# rapidshark-forward-breakout-mk-1_1.net
KiCad netlist of a schematic drawn in EAGLE
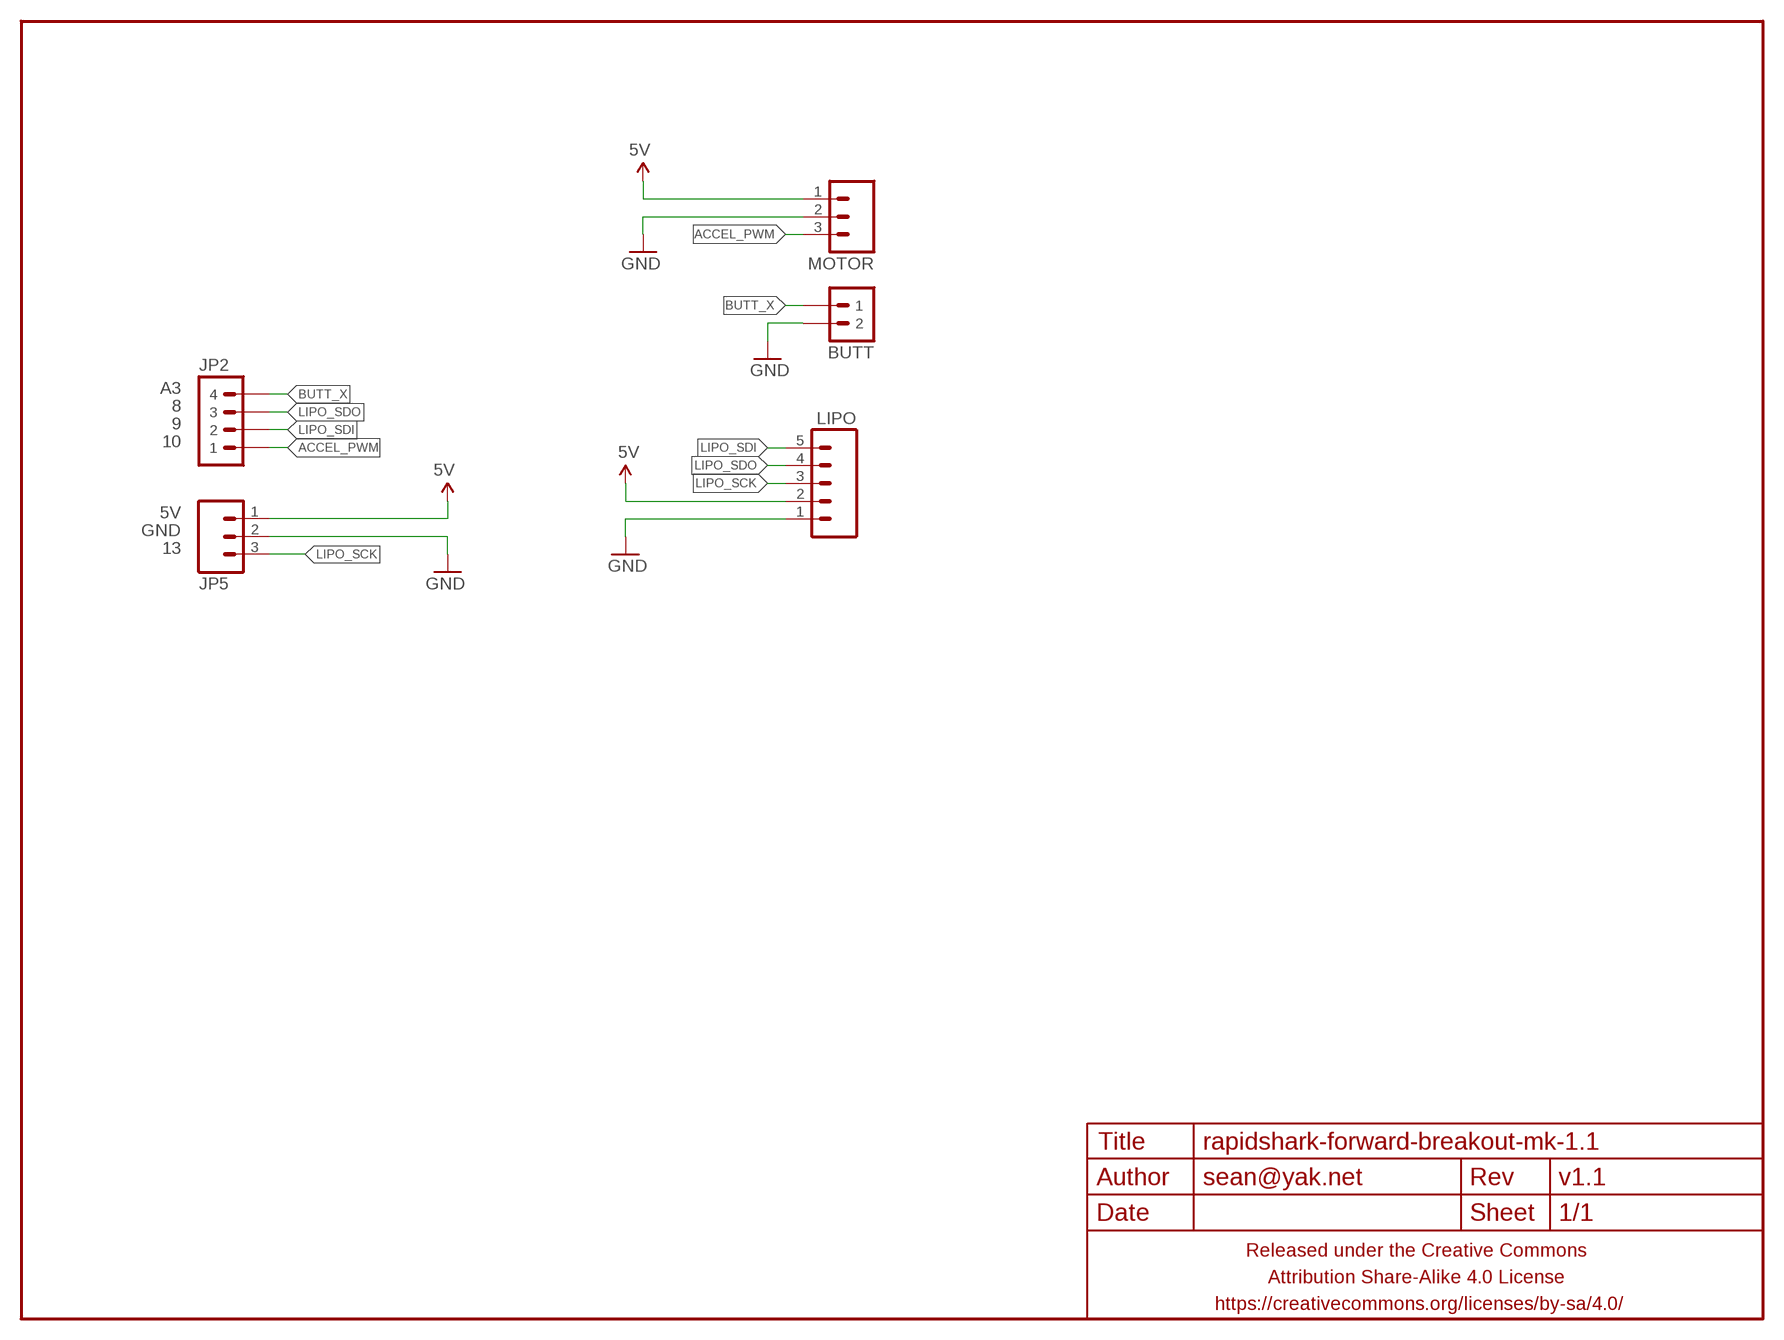
[diagram p0: schematic, sheet 1]

(export (version "E")
  (design (tool "Eeschema 10.0.6"))
  (components
    (comp (ref "BUTT")
      (value "M02JST-PTH-VERT")
      (footprint "eagle-import:JST-2-PH-VERT-PTH")
      (libsource (lib "eagle-import") (part "M02JST-PTH-VERT"))
    )
    (comp (ref "FRAME1")
      (value "FRAME-LETTERNO_PACKAGE")
      (footprint "eagle-import:DUMMY")
      (fields (field (name "DESIGNER") "sean@yak.net") (field (name "VERSION") "v1.1"))
      (libsource (lib "eagle-import") (part "FRAME-LETTERNO_PACKAGE"))
    )
    (comp (ref "JP2")
      (value "M04JST-PTH-VERT")
      (footprint "eagle-import:JST-4-PH-VERT-PTH")
      (libsource (lib "eagle-import") (part "M04JST-PTH-VERT"))
    )
    (comp (ref "JP5")
      (value "M03JST-PTH-VERT")
      (footprint "eagle-import:JST-3-PH-VERT-PTH")
      (libsource (lib "eagle-import") (part "M03JST-PTH-VERT"))
    )
    (comp (ref "LIPO")
      (value "M05JST-PH-VERT-PTH")
      (footprint "eagle-import:JST-5-PH-VERT-PTH")
      (libsource (lib "eagle-import") (part "M05JST-PH-VERT-PTH"))
    )
    (comp (ref "MOTOR")
      (value "M03JST-PTH-VERT")
      (footprint "eagle-import:JST-3-PH-VERT-PTH")
      (libsource (lib "eagle-import") (part "M03JST-PTH-VERT"))
    )
  )
  (nets
    (net (code "1") (name "5V") (class "Default")
      (node (ref "JP5") (pin "1") (pinfunction "1_1") (pintype "passive"))
      (node (ref "LIPO") (pin "2") (pinfunction "2_2") (pintype "passive"))
      (node (ref "MOTOR") (pin "1") (pinfunction "1_1") (pintype "passive"))
    )
    (net (code "2") (name "ACCEL_PWM") (class "Default")
      (node (ref "JP2") (pin "1") (pinfunction "1_1") (pintype "passive"))
      (node (ref "MOTOR") (pin "3") (pinfunction "3_3") (pintype "passive"))
    )
    (net (code "3") (name "BUTT_X") (class "Default")
      (node (ref "BUTT") (pin "1") (pinfunction "1_1") (pintype "passive"))
      (node (ref "JP2") (pin "4") (pinfunction "4_4") (pintype "passive"))
    )
    (net (code "4") (name "GND") (class "Default")
      (node (ref "BUTT") (pin "2") (pinfunction "2_2") (pintype "passive"))
      (node (ref "JP5") (pin "2") (pinfunction "2_2") (pintype "passive"))
      (node (ref "LIPO") (pin "1") (pinfunction "1_1") (pintype "passive"))
      (node (ref "MOTOR") (pin "2") (pinfunction "2_2") (pintype "passive"))
    )
    (net (code "5") (name "LIPO_SCK") (class "Default")
      (node (ref "JP5") (pin "3") (pinfunction "3_3") (pintype "passive"))
      (node (ref "LIPO") (pin "3") (pinfunction "3_3") (pintype "passive"))
    )
    (net (code "6") (name "LIPO_SDI") (class "Default")
      (node (ref "JP2") (pin "2") (pinfunction "2_2") (pintype "passive"))
      (node (ref "LIPO") (pin "5") (pinfunction "5_5") (pintype "passive"))
    )
    (net (code "7") (name "LIPO_SDO") (class "Default")
      (node (ref "JP2") (pin "3") (pinfunction "3_3") (pintype "passive"))
      (node (ref "LIPO") (pin "4") (pinfunction "4_4") (pintype "passive"))
    )
  )
)
